# rs232_12V_step_Vadim.net
KiCad netlist of a schematic drawn in Altium Designer
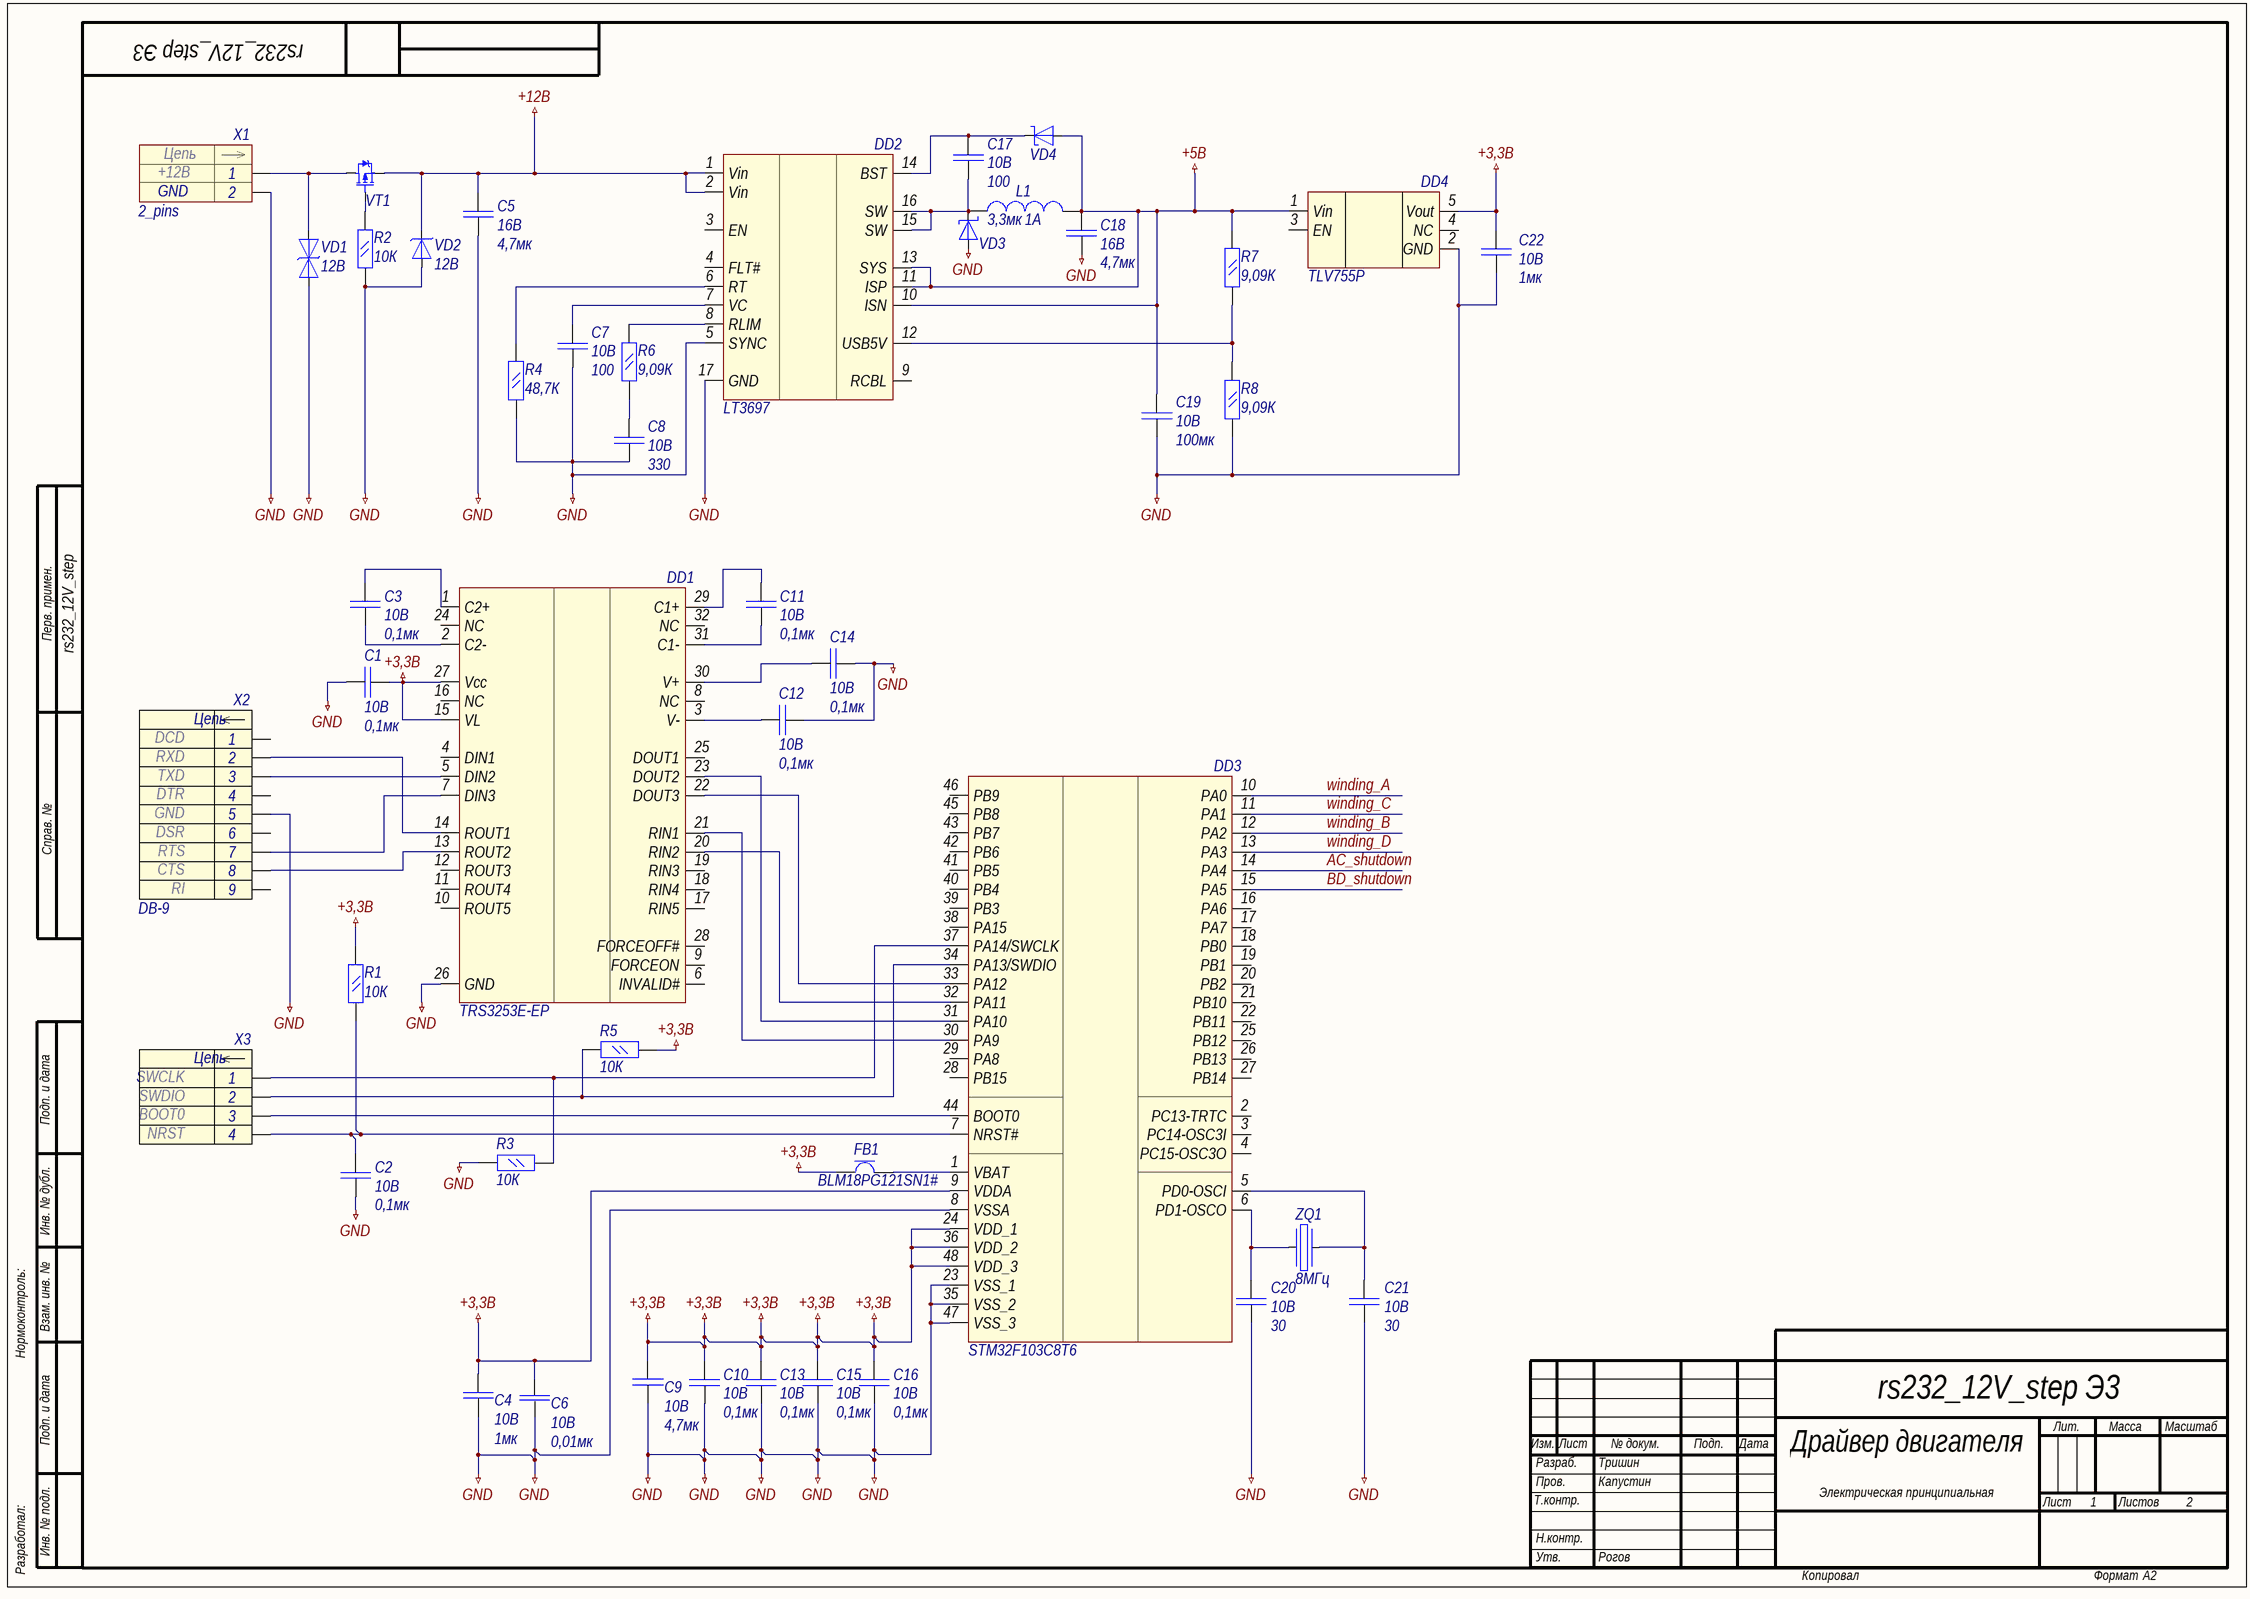
[diagram p0: rs232_12V_step_Vadim.SchDoc]

(export (version "E")
  (design (tool "Eeschema 10.0.6"))
  (components
    (comp (ref "C1")
      (value "Capacitor")
      (footprint "CH0402C")
      (fields (field (name "VOLTAGE") "10В") (field (name "CAPACITANCE") "0,1мк"))
      (libsource (lib "GOST_Capacitors") (part "Capacitor"))
    )
    (comp (ref "C2")
      (value "Capacitor")
      (footprint "CH0402C")
      (fields (field (name "VOLTAGE") "10В") (field (name "CAPACITANCE") "0,1мк"))
      (libsource (lib "GOST_Capacitors") (part "Capacitor"))
    )
    (comp (ref "C3")
      (value "Capacitor")
      (footprint "CH0402C")
      (fields (field (name "VOLTAGE") "10В") (field (name "CAPACITANCE") "0,1мк"))
      (libsource (lib "GOST_Capacitors") (part "Capacitor"))
    )
    (comp (ref "C4")
      (value "Capacitor")
      (footprint "CH0201C")
      (fields (field (name "VOLTAGE") "10В") (field (name "CAPACITANCE") "1мк"))
      (libsource (lib "GOST_Capacitors") (part "Capacitor"))
    )
    (comp (ref "C5")
      (value "Capacitor")
      (footprint "CH0603C")
      (fields (field (name "VOLTAGE") "16В") (field (name "CAPACITANCE") "4,7мк"))
      (libsource (lib "GOST_Capacitors") (part "Capacitor"))
    )
    (comp (ref "C6")
      (value "Capacitor")
      (footprint "CH0402C")
      (fields (field (name "VOLTAGE") "10В") (field (name "CAPACITANCE") "0,01мк"))
      (libsource (lib "") (part "Capacitor_1"))
    )
    (comp (ref "C7")
      (value "Capacitor")
      (footprint "CH0201C")
      (fields (field (name "VOLTAGE") "10В") (field (name "CAPACITANCE") "100"))
      (libsource (lib "GOST_Capacitors") (part "Capacitor"))
    )
    (comp (ref "C8")
      (value "Capacitor")
      (footprint "CH0402C")
      (fields (field (name "VOLTAGE") "10В") (field (name "CAPACITANCE") "330"))
      (libsource (lib "GOST_Capacitors") (part "Capacitor"))
    )
    (comp (ref "C9")
      (value "Capacitor")
      (footprint "CH0402C")
      (fields (field (name "VOLTAGE") "10В") (field (name "CAPACITANCE") "4,7мк"))
      (libsource (lib "GOST_Capacitors") (part "Capacitor"))
    )
    (comp (ref "C10")
      (value "Capacitor")
      (footprint "CH0402C")
      (fields (field (name "VOLTAGE") "10В") (field (name "CAPACITANCE") "0,1мк"))
      (libsource (lib "GOST_Capacitors") (part "Capacitor"))
    )
    (comp (ref "C11")
      (value "Capacitor")
      (footprint "CH0402C")
      (fields (field (name "VOLTAGE") "10В") (field (name "CAPACITANCE") "0,1мк"))
      (libsource (lib "GOST_Capacitors") (part "Capacitor"))
    )
    (comp (ref "C12")
      (value "Capacitor")
      (footprint "CH0402C")
      (fields (field (name "VOLTAGE") "10В") (field (name "CAPACITANCE") "0,1мк"))
      (libsource (lib "GOST_Capacitors") (part "Capacitor"))
    )
    (comp (ref "C13")
      (value "Capacitor")
      (footprint "CH0402C")
      (fields (field (name "VOLTAGE") "10В") (field (name "CAPACITANCE") "0,1мк"))
      (libsource (lib "GOST_Capacitors") (part "Capacitor"))
    )
    (comp (ref "C14")
      (value "Capacitor")
      (footprint "CH0402C")
      (fields (field (name "VOLTAGE") "10В") (field (name "CAPACITANCE") "0,1мк"))
      (libsource (lib "GOST_Capacitors") (part "Capacitor"))
    )
    (comp (ref "C15")
      (value "Capacitor")
      (footprint "CH0402C")
      (fields (field (name "VOLTAGE") "10В") (field (name "CAPACITANCE") "0,1мк"))
      (libsource (lib "GOST_Capacitors") (part "Capacitor"))
    )
    (comp (ref "C16")
      (value "Capacitor")
      (footprint "CH0402C")
      (fields (field (name "VOLTAGE") "10В") (field (name "CAPACITANCE") "0,1мк"))
      (libsource (lib "GOST_Capacitors") (part "Capacitor"))
    )
    (comp (ref "C17")
      (value "Capacitor")
      (footprint "CH0201C")
      (fields (field (name "VOLTAGE") "10В") (field (name "CAPACITANCE") "100"))
      (libsource (lib "GOST_Capacitors") (part "Capacitor"))
    )
    (comp (ref "C18")
      (value "Capacitor")
      (footprint "CH0603C")
      (fields (field (name "VOLTAGE") "16В") (field (name "CAPACITANCE") "4,7мк"))
      (libsource (lib "GOST_Capacitors") (part "Capacitor"))
    )
    (comp (ref "C19")
      (value "Capacitor")
      (footprint "CH1206C")
      (fields (field (name "VOLTAGE") "10В") (field (name "CAPACITANCE") "100мк"))
      (libsource (lib "GOST_Capacitors") (part "Capacitor"))
    )
    (comp (ref "C20")
      (value "Capacitor")
      (footprint "CH0201C")
      (fields (field (name "VOLTAGE") "10В") (field (name "CAPACITANCE") "30"))
      (libsource (lib "GOST_Capacitors") (part "Capacitor"))
    )
    (comp (ref "C21")
      (value "Capacitor")
      (footprint "CH0201C")
      (fields (field (name "VOLTAGE") "10В") (field (name "CAPACITANCE") "30"))
      (libsource (lib "GOST_Capacitors") (part "Capacitor"))
    )
    (comp (ref "C22")
      (value "Capacitor")
      (footprint "CH0201C")
      (fields (field (name "VOLTAGE") "10В") (field (name "CAPACITANCE") "1мк"))
      (libsource (lib "GOST_Capacitors") (part "Capacitor"))
    )
    (comp (ref "DD1")
      (value "TRS3253E-EP")
      (footprint "TRS3253E-EP")
      (description "UART - RS232")
      (libsource (lib "GOST_lib_devices") (part "TRS3253E-EP"))
    )
    (comp (ref "DD2")
      (value "LT3697")
      (footprint "LT3697")
      (description "6~18 to 5")
      (libsource (lib "GOST_lib_devices") (part "LT3697"))
    )
    (comp (ref "DD3")
      (value "STM32F103C8T6")
      (footprint "STM32F103 48pins")
      (libsource (lib "GOST_lib_devices") (part "STM32"))
    )
    (comp (ref "DD4")
      (value "TLV755P")
      (footprint "SOT23-5")
      (libsource (lib "GOST_lib_devices") (part "LDO +3.3V"))
    )
    (comp (ref "FB1")
      (value "Ferrite bead")
      (footprint "CH0603L")
      (fields (field (name "MODEL") "BLM18PG121SN1#"))
      (libsource (lib "GOST_Inductors") (part "Ferrite bead"))
    )
    (comp (ref "L1")
      (value "*")
      (footprint "CH0805L")
      (fields (field (name "MAX CURRENT") "1А") (field (name "INDUCTANCE") "3,3мк"))
      (libsource (lib "GOST_Inductors") (part "Inductor"))
    )
    (comp (ref "R1")
      (value "Res_0.125")
      (footprint "CH0805R")
      (fields (field (name "IMPEDANCE") "10К"))
      (libsource (lib "GOST_Resistors") (part "Res_0.125"))
    )
    (comp (ref "R2")
      (value "Res_0.125")
      (footprint "CH0402R")
      (fields (field (name "IMPEDANCE") "10К"))
      (libsource (lib "GOST_Resistors") (part "Res_0.125"))
    )
    (comp (ref "R3")
      (value "Res_0.125")
      (footprint "CH0805R")
      (fields (field (name "IMPEDANCE") "10К"))
      (libsource (lib "GOST_Resistors") (part "Res_0.125"))
    )
    (comp (ref "R4")
      (value "Res_0.125")
      (footprint "CH0805R")
      (fields (field (name "IMPEDANCE") "48,7К"))
      (libsource (lib "GOST_Resistors") (part "Res_0.125"))
    )
    (comp (ref "R5")
      (value "Res_0.125")
      (footprint "CH0805R")
      (fields (field (name "IMPEDANCE") "10К"))
      (libsource (lib "GOST_Resistors") (part "Res_0.125"))
    )
    (comp (ref "R6")
      (value "Res_0.125")
      (footprint "CH0805R")
      (fields (field (name "IMPEDANCE") "9,09К"))
      (libsource (lib "GOST_Resistors") (part "Res_0.125"))
    )
    (comp (ref "R7")
      (value "Res_0.125")
      (footprint "CH0805R")
      (fields (field (name "IMPEDANCE") "9,09К"))
      (libsource (lib "GOST_Resistors") (part "Res_0.125"))
    )
    (comp (ref "R8")
      (value "Res_0.125")
      (footprint "CH0805R")
      (fields (field (name "IMPEDANCE") "9,09К"))
      (libsource (lib "GOST_Resistors") (part "Res_0.125"))
    )
    (comp (ref "VD1")
      (value "TVS-diod_simmetrical")
      (footprint "CH0201L")
      (fields (field (name "MANUFACTURER") "Littelfuse") (field (name "CLAMPING VOLTAGE") "12В"))
      (libsource (lib "GOST_Diodes") (part "TVS-diod_simmetrical"))
    )
    (comp (ref "VD2")
      (value "TVS-diod_directed")
      (footprint "DO214AA")
      (fields (field (name "MANUFACTURER") "Bourns") (field (name "CLAMPING_VOLTAGE") "12В"))
      (libsource (lib "GOST_Diodes") (part "TVS-diod_directed"))
    )
    (comp (ref "VD3")
      (value "Diod Schottky")
      (footprint "DO214AA")
      (fields (field (name "MANUFACTURER") "Rectron"))
      (libsource (lib "GOST_Diodes") (part "Diod Schottky"))
    )
    (comp (ref "VD4")
      (value "Diod Schottky")
      (footprint "SOT23_132")
      (fields (field (name "MANUFACTURER") "Toshiba"))
      (libsource (lib "GOST_Diodes") (part "Diod Schottky"))
    )
    (comp (ref "VT1")
      (value "*")
      (footprint "SOT23_132")
      (libsource (lib "GOST_Transistors") (part "P-Channel"))
    )
    (comp (ref "X1")
      (value "2_pins")
      (footprint "CON: 163-179PH-EX")
      (fields (field (name "VCC") "+12В"))
      (libsource (lib "GOST_lib_connectors") (part "2_pins"))
    )
    (comp (ref "X2")
      (value "DB-9")
      (footprint "CON: DB-9F")
      (fields
        (field (name "1") "DCD")
        (field (name "2") "RXD")
        (field (name "3") "TXD")
        (field (name "4") "DTR")
        (field (name "5") "GND")
        (field (name "6") "DSR")
        (field (name "7") "RTS")
        (field (name "8") "CTS")
        (field (name "9") "RI")
      )
      (libsource (lib "GOST_lib_connectors") (part "9_pins"))
    )
    (comp (ref "X3")
      (value "4_pins")
      (footprint "CON: CWF-4R")
      (fields
        (field (name "2") "SWDIO")
        (field (name "3") "BOOT0")
        (field (name "1") "SWCLK")
        (field (name "4") "NRST")
      )
      (libsource (lib "GOST_lib_connectors") (part "4_pins"))
    )
    (comp (ref "ZQ1")
      (value "Oscillator")
      (footprint "OSC: 5032")
      (fields (field (name "FREQ") "8МГц"))
      (libsource (lib "GOST_Miscelanuious") (part "Oscillator"))
    )
  )
  (nets
    (net (code "1") (name "+3,3В") (class "Default")
      (node (ref "C1") (pin "2") (pinfunction "C1-_2") (pintype "power_in"))
      (node (ref "C10") (pin "1") (pinfunction "C1+_1") (pintype "power_in"))
      (node (ref "C13") (pin "1") (pinfunction "C1+_1") (pintype "power_in"))
      (node (ref "C15") (pin "1") (pinfunction "C1+_1") (pintype "power_in"))
      (node (ref "C16") (pin "1") (pinfunction "C1+_1") (pintype "power_in"))
      (node (ref "C22") (pin "1") (pinfunction "C1+_1") (pintype "power_in"))
      (node (ref "C4") (pin "2") (pinfunction "C1-_2") (pintype "power_in"))
      (node (ref "C6") (pin "1") (pinfunction "С+_1") (pintype "power_in"))
      (node (ref "C9") (pin "2") (pinfunction "C1-_2") (pintype "power_in"))
      (node (ref "DD1") (pin "15") (pinfunction "VL_15") (pintype "power_in"))
      (node (ref "DD1") (pin "27") (pinfunction "Vcc_27") (pintype "power_in"))
      (node (ref "DD3") (pin "24") (pinfunction "VDD_1_24") (pintype "passive"))
      (node (ref "DD3") (pin "36") (pinfunction "VDD_2_36") (pintype "passive"))
      (node (ref "DD3") (pin "48") (pinfunction "VDD_3_48") (pintype "passive"))
      (node (ref "DD3") (pin "9") (pinfunction "VDDA_9") (pintype "passive"))
      (node (ref "DD4") (pin "5") (pinfunction "Vout_5") (pintype "power_in"))
      (node (ref "FB1") (pin "1") (pintype "power_in"))
      (node (ref "R1") (pin "1") (pinfunction "C1-_1") (pintype "power_in"))
      (node (ref "R5") (pin "2") (pinfunction "C1-_2") (pintype "power_in"))
    )
    (net (code "2") (name "+5В") (class "Default")
      (node (ref "C18") (pin "1") (pinfunction "C1+_1") (pintype "power_in"))
      (node (ref "C19") (pin "1") (pinfunction "C1+_1") (pintype "power_in"))
      (node (ref "DD2") (pin "10") (pinfunction "ISN_10") (pintype "power_in"))
      (node (ref "DD2") (pin "11") (pinfunction "ISP_11") (pintype "power_in"))
      (node (ref "DD2") (pin "13") (pinfunction "SYS_13") (pintype "power_in"))
      (node (ref "DD4") (pin "1") (pinfunction "Vin_1") (pintype "power_in"))
      (node (ref "L1") (pin "2") (pinfunction "14_2") (pintype "power_in"))
      (node (ref "R7") (pin "1") (pinfunction "C1-_1") (pintype "power_in"))
      (node (ref "VD4") (pin "1") (pinfunction "1_1") (pintype "passive"))
    )
    (net (code "3") (name "+12В") (class "Default")
      (node (ref "C5") (pin "1") (pinfunction "C1+_1") (pintype "power_in"))
      (node (ref "DD2") (pin "1") (pinfunction "Vin_1") (pintype "power_in"))
      (node (ref "DD2") (pin "2") (pinfunction "Vin_2") (pintype "power_in"))
      (node (ref "VD2") (pin "2") (pinfunction "C_2") (pintype "passive"))
      (node (ref "VT1") (pin "3") (pinfunction "S_3") (pintype "passive"))
    )
    (net (code "4") (name "/AC_shutdown") (class "Default")
      (node (ref "DD3") (pin "14") (pinfunction "PA4_14") (pintype "passive"))
    )
    (net (code "5") (name "/BD_shutdown") (class "Default")
      (node (ref "DD3") (pin "15") (pinfunction "PA5_15") (pintype "passive"))
    )
    (net (code "6") (name "/winding_A") (class "Default")
      (node (ref "DD3") (pin "10") (pinfunction "PA0_10") (pintype "passive"))
    )
    (net (code "7") (name "/winding_B") (class "Default")
      (node (ref "DD3") (pin "12") (pinfunction "PA2_12") (pintype "passive"))
    )
    (net (code "8") (name "/winding_C") (class "Default")
      (node (ref "DD3") (pin "11") (pinfunction "PA1_11") (pintype "passive"))
    )
    (net (code "9") (name "/winding_D") (class "Default")
      (node (ref "DD3") (pin "13") (pinfunction "PA3_13") (pintype "passive"))
    )
    (net (code "10") (name "GND") (class "Default")
      (node (ref "C1") (pin "1") (pinfunction "C1+_1") (pintype "power_in"))
      (node (ref "C10") (pin "2") (pinfunction "C1-_2") (pintype "power_in"))
      (node (ref "C12") (pin "2") (pinfunction "C1-_2") (pintype "power_in"))
      (node (ref "C13") (pin "2") (pinfunction "C1-_2") (pintype "power_in"))
      (node (ref "C14") (pin "2") (pinfunction "C1-_2") (pintype "power_in"))
      (node (ref "C15") (pin "2") (pinfunction "C1-_2") (pintype "power_in"))
      (node (ref "C16") (pin "2") (pinfunction "C1-_2") (pintype "power_in"))
      (node (ref "C18") (pin "2") (pinfunction "C1-_2") (pintype "power_in"))
      (node (ref "C19") (pin "2") (pinfunction "C1-_2") (pintype "power_in"))
      (node (ref "C2") (pin "2") (pinfunction "C1-_2") (pintype "power_in"))
      (node (ref "C20") (pin "2") (pinfunction "C1-_2") (pintype "power_in"))
      (node (ref "C21") (pin "2") (pinfunction "C1-_2") (pintype "power_in"))
      (node (ref "C22") (pin "2") (pinfunction "C1-_2") (pintype "power_in"))
      (node (ref "C4") (pin "1") (pinfunction "C1+_1") (pintype "power_in"))
      (node (ref "C5") (pin "2") (pinfunction "C1-_2") (pintype "power_in"))
      (node (ref "C6") (pin "2") (pinfunction "С-_2") (pintype "power_in"))
      (node (ref "C7") (pin "2") (pinfunction "C1-_2") (pintype "power_in"))
      (node (ref "C8") (pin "2") (pinfunction "C1-_2") (pintype "power_in"))
      (node (ref "C9") (pin "1") (pinfunction "C1+_1") (pintype "power_in"))
      (node (ref "DD1") (pin "26") (pinfunction "GND_26") (pintype "power_in"))
      (node (ref "DD2") (pin "17") (pinfunction "GND_17") (pintype "power_in"))
      (node (ref "DD2") (pin "5") (pinfunction "SYNC_5") (pintype "power_in"))
      (node (ref "DD3") (pin "23") (pinfunction "VSS_1_23") (pintype "passive"))
      (node (ref "DD3") (pin "35") (pinfunction "VSS_2_35") (pintype "passive"))
      (node (ref "DD3") (pin "47") (pinfunction "VSS_3_47") (pintype "passive"))
      (node (ref "DD3") (pin "8") (pinfunction "VSSA_8") (pintype "passive"))
      (node (ref "DD4") (pin "2") (pinfunction "GND_2") (pintype "power_in"))
      (node (ref "R2") (pin "1") (pinfunction "C1-_1") (pintype "power_in"))
      (node (ref "R3") (pin "1") (pinfunction "C1-_1") (pintype "power_in"))
      (node (ref "R4") (pin "2") (pinfunction "C1-_2") (pintype "power_in"))
      (node (ref "R8") (pin "2") (pinfunction "C1-_2") (pintype "power_in"))
      (node (ref "VD1") (pin "1") (pinfunction "A_1") (pintype "passive"))
      (node (ref "VD2") (pin "1") (pinfunction "A_1") (pintype "passive"))
      (node (ref "VD3") (pin "1") (pinfunction "1_1") (pintype "passive"))
      (node (ref "X1") (pin "2") (pinfunction "2_2") (pintype "passive"))
      (node (ref "X2") (pin "5") (pinfunction "5_5") (pintype "passive"))
    )
    (net (code "11") (name "Net-(C2-C1+)") (class "Default")
      (node (ref "C2") (pin "1") (pinfunction "C1+_1") (pintype "power_in"))
      (node (ref "DD3") (pin "7") (pinfunction "NRST#_7") (pintype "passive"))
      (node (ref "R1") (pin "2") (pinfunction "C1-_2") (pintype "power_in"))
      (node (ref "X3") (pin "4") (pinfunction "4_4") (pintype "passive"))
    )
    (net (code "12") (name "Net-(C3-C1+)") (class "Default")
      (node (ref "C3") (pin "1") (pinfunction "C1+_1") (pintype "power_in"))
      (node (ref "DD1") (pin "1") (pinfunction "C2+_1") (pintype "power_in"))
    )
    (net (code "13") (name "Net-(C3-C1-)") (class "Default")
      (node (ref "C3") (pin "2") (pinfunction "C1-_2") (pintype "power_in"))
      (node (ref "DD1") (pin "2") (pinfunction "C2-_2") (pintype "power_in"))
    )
    (net (code "14") (name "Net-(C7-C1+)") (class "Default")
      (node (ref "C7") (pin "1") (pinfunction "C1+_1") (pintype "power_in"))
      (node (ref "DD2") (pin "7") (pinfunction "VC_7") (pintype "power_in"))
    )
    (net (code "15") (name "Net-(C8-C1+)") (class "Default")
      (node (ref "C8") (pin "1") (pinfunction "C1+_1") (pintype "power_in"))
      (node (ref "R6") (pin "2") (pinfunction "C1-_2") (pintype "power_in"))
    )
    (net (code "16") (name "Net-(C11-C1+)") (class "Default")
      (node (ref "C11") (pin "1") (pinfunction "C1+_1") (pintype "power_in"))
      (node (ref "DD1") (pin "29") (pinfunction "C1+_29") (pintype "power_in"))
    )
    (net (code "17") (name "Net-(C11-C1-)") (class "Default")
      (node (ref "C11") (pin "2") (pinfunction "C1-_2") (pintype "power_in"))
      (node (ref "DD1") (pin "31") (pinfunction "C1-_31") (pintype "power_in"))
    )
    (net (code "18") (name "Net-(C12-C1+)") (class "Default")
      (node (ref "C12") (pin "1") (pinfunction "C1+_1") (pintype "power_in"))
      (node (ref "DD1") (pin "3") (pinfunction "V-_3") (pintype "power_in"))
    )
    (net (code "19") (name "Net-(C14-C1+)") (class "Default")
      (node (ref "C14") (pin "1") (pinfunction "C1+_1") (pintype "power_in"))
      (node (ref "DD1") (pin "30") (pinfunction "V+_30") (pintype "power_in"))
    )
    (net (code "20") (name "Net-(C17-C1+)") (class "Default")
      (node (ref "C17") (pin "1") (pinfunction "C1+_1") (pintype "power_in"))
      (node (ref "DD2") (pin "14") (pinfunction "BST_14") (pintype "power_in"))
      (node (ref "VD4") (pin "2") (pinfunction "2_2") (pintype "passive"))
    )
    (net (code "21") (name "Net-(C17-C1-)") (class "Default")
      (node (ref "C17") (pin "2") (pinfunction "C1-_2") (pintype "power_in"))
      (node (ref "DD2") (pin "15") (pinfunction "SW_15") (pintype "power_in"))
      (node (ref "DD2") (pin "16") (pinfunction "SW_16") (pintype "power_in"))
      (node (ref "L1") (pin "1") (pinfunction "C1-_1") (pintype "power_in"))
      (node (ref "VD3") (pin "2") (pinfunction "2_2") (pintype "passive"))
    )
    (net (code "22") (name "Net-(C20-C1+)") (class "Default")
      (node (ref "C20") (pin "1") (pinfunction "C1+_1") (pintype "power_in"))
      (node (ref "DD3") (pin "6") (pinfunction "PD1-OSCO_6") (pintype "passive"))
      (node (ref "ZQ1") (pin "1") (pintype "passive"))
    )
    (net (code "23") (name "Net-(C21-C1+)") (class "Default")
      (node (ref "C21") (pin "1") (pinfunction "C1+_1") (pintype "power_in"))
      (node (ref "DD3") (pin "5") (pinfunction "PD0-OSCI_5") (pintype "passive"))
      (node (ref "ZQ1") (pin "3") (pintype "passive"))
    )
    (net (code "24") (name "Net-(DD1-DIN2)") (class "Default")
      (node (ref "DD1") (pin "5") (pinfunction "DIN2_5") (pintype "power_in"))
      (node (ref "X2") (pin "3") (pinfunction "3_3") (pintype "passive"))
    )
    (net (code "25") (name "Net-(DD1-DIN3)") (class "Default")
      (node (ref "DD1") (pin "7") (pinfunction "DIN3_7") (pintype "power_in"))
      (node (ref "X2") (pin "7") (pinfunction "7_7") (pintype "power_in"))
    )
    (net (code "26") (name "Net-(DD1-DOUT2)") (class "Default")
      (node (ref "DD1") (pin "23") (pinfunction "DOUT2_23") (pintype "power_in"))
      (node (ref "DD3") (pin "31") (pinfunction "PA10_31") (pintype "passive"))
    )
    (net (code "27") (name "Net-(DD1-DOUT3)") (class "Default")
      (node (ref "DD1") (pin "22") (pinfunction "DOUT3_22") (pintype "power_in"))
      (node (ref "DD3") (pin "33") (pinfunction "PA12_33") (pintype "passive"))
    )
    (net (code "28") (name "Net-(DD1-RIN1)") (class "Default")
      (node (ref "DD1") (pin "21") (pinfunction "RIN1_21") (pintype "power_in"))
      (node (ref "DD3") (pin "30") (pinfunction "PA9_30") (pintype "passive"))
    )
    (net (code "29") (name "Net-(DD1-RIN2)") (class "Default")
      (node (ref "DD1") (pin "20") (pinfunction "RIN2_20") (pintype "power_in"))
      (node (ref "DD3") (pin "32") (pinfunction "PA11_32") (pintype "passive"))
    )
    (net (code "30") (name "Net-(DD1-ROUT1)") (class "Default")
      (node (ref "DD1") (pin "14") (pinfunction "ROUT1_14") (pintype "power_in"))
      (node (ref "X2") (pin "2") (pinfunction "2_2") (pintype "passive"))
    )
    (net (code "31") (name "Net-(DD1-ROUT2)") (class "Default")
      (node (ref "DD1") (pin "13") (pinfunction "ROUT2_13") (pintype "power_in"))
      (node (ref "X2") (pin "8") (pinfunction "8_8") (pintype "power_in"))
    )
    (net (code "32") (name "Net-(DD2-RLIM)") (class "Default")
      (node (ref "DD2") (pin "8") (pinfunction "RLIM_8") (pintype "power_in"))
      (node (ref "R6") (pin "1") (pinfunction "C1-_1") (pintype "power_in"))
    )
    (net (code "33") (name "Net-(DD2-RT)") (class "Default")
      (node (ref "DD2") (pin "6") (pinfunction "RT_6") (pintype "power_in"))
      (node (ref "R4") (pin "1") (pinfunction "C1-_1") (pintype "power_in"))
    )
    (net (code "34") (name "Net-(DD2-USB5V)") (class "Default")
      (node (ref "DD2") (pin "12") (pinfunction "USB5V_12") (pintype "power_in"))
      (node (ref "R7") (pin "2") (pinfunction "C1-_2") (pintype "power_in"))
      (node (ref "R8") (pin "1") (pinfunction "C1-_1") (pintype "power_in"))
    )
    (net (code "35") (name "Net-(DD3-BOOT0)") (class "Default")
      (node (ref "DD3") (pin "44") (pinfunction "BOOT0_44") (pintype "passive"))
      (node (ref "X3") (pin "3") (pinfunction "3_3") (pintype "passive"))
    )
    (net (code "36") (name "Net-(DD3-PA13{slash}SWDIO)") (class "Default")
      (node (ref "DD3") (pin "34") (pinfunction "PA13/SWDIO_34") (pintype "passive"))
      (node (ref "R5") (pin "1") (pinfunction "C1-_1") (pintype "power_in"))
      (node (ref "X3") (pin "2") (pinfunction "2_2") (pintype "passive"))
    )
    (net (code "37") (name "Net-(DD3-PA14{slash}SWCLK)") (class "Default")
      (node (ref "DD3") (pin "37") (pinfunction "PA14/SWCLK_37") (pintype "passive"))
      (node (ref "R3") (pin "2") (pinfunction "C1-_2") (pintype "power_in"))
      (node (ref "X3") (pin "1") (pinfunction "1_1") (pintype "passive"))
    )
    (net (code "38") (name "Net-(DD3-VBAT)") (class "Default")
      (node (ref "DD3") (pin "1") (pinfunction "VBAT_1") (pintype "passive"))
      (node (ref "FB1") (pin "2") (pintype "power_in"))
    )
    (net (code "39") (name "Net-(VD1-C)") (class "Default")
      (node (ref "VD1") (pin "2") (pinfunction "C_2") (pintype "passive"))
      (node (ref "VT1") (pin "2") (pinfunction "D_2") (pintype "passive"))
      (node (ref "X1") (pin "1") (pinfunction "1_1") (pintype "passive"))
    )
    (net (code "40") (name "Net-(VT1-G)") (class "Default")
      (node (ref "R2") (pin "2") (pinfunction "C1-_2") (pintype "power_in"))
      (node (ref "VT1") (pin "1") (pinfunction "G_1") (pintype "passive"))
    )
    (net (code "41") (name "unconnected-(DD1-DIN1-Pad4)") (class "Default")
      (node (ref "DD1") (pin "4") (pinfunction "DIN1_4") (pintype "power_in"))
    )
    (net (code "42") (name "unconnected-(DD1-DOUT1-Pad25)") (class "Default")
      (node (ref "DD1") (pin "25") (pinfunction "DOUT1_25") (pintype "power_in"))
    )
    (net (code "43") (name "unconnected-(DD1-FORCEOFF#-Pad28)") (class "Default")
      (node (ref "DD1") (pin "28") (pinfunction "FORCEOFF#_28") (pintype "power_in"))
    )
    (net (code "44") (name "unconnected-(DD1-FORCEON-Pad9)") (class "Default")
      (node (ref "DD1") (pin "9") (pinfunction "FORCEON_9") (pintype "power_in"))
    )
    (net (code "45") (name "unconnected-(DD1-INVALID#-Pad6)") (class "Default")
      (node (ref "DD1") (pin "6") (pinfunction "INVALID#_6") (pintype "power_in"))
    )
    (net (code "46") (name "unconnected-(DD1-NC-Pad8)") (class "Default")
      (node (ref "DD1") (pin "8") (pinfunction "NC_8") (pintype "power_in"))
    )
    (net (code "47") (name "unconnected-(DD1-NC-Pad16)") (class "Default")
      (node (ref "DD1") (pin "16") (pinfunction "NC_16") (pintype "power_in"))
    )
    (net (code "48") (name "unconnected-(DD1-NC-Pad24)") (class "Default")
      (node (ref "DD1") (pin "24") (pinfunction "NC_24") (pintype "power_in"))
    )
    (net (code "49") (name "unconnected-(DD1-NC-Pad32)") (class "Default")
      (node (ref "DD1") (pin "32") (pinfunction "NC_32") (pintype "power_in"))
    )
    (net (code "50") (name "unconnected-(DD1-RIN3-Pad19)") (class "Default")
      (node (ref "DD1") (pin "19") (pinfunction "RIN3_19") (pintype "power_in"))
    )
    (net (code "51") (name "unconnected-(DD1-RIN4-Pad18)") (class "Default")
      (node (ref "DD1") (pin "18") (pinfunction "RIN4_18") (pintype "power_in"))
    )
    (net (code "52") (name "unconnected-(DD1-RIN5-Pad17)") (class "Default")
      (node (ref "DD1") (pin "17") (pinfunction "RIN5_17") (pintype "power_in"))
    )
    (net (code "53") (name "unconnected-(DD1-ROUT3-Pad12)") (class "Default")
      (node (ref "DD1") (pin "12") (pinfunction "ROUT3_12") (pintype "power_in"))
    )
    (net (code "54") (name "unconnected-(DD1-ROUT4-Pad11)") (class "Default")
      (node (ref "DD1") (pin "11") (pinfunction "ROUT4_11") (pintype "power_in"))
    )
    (net (code "55") (name "unconnected-(DD1-ROUT5-Pad10)") (class "Default")
      (node (ref "DD1") (pin "10") (pinfunction "ROUT5_10") (pintype "power_in"))
    )
    (net (code "56") (name "unconnected-(DD2-EN-Pad3)") (class "Default")
      (node (ref "DD2") (pin "3") (pinfunction "EN_3") (pintype "power_in"))
    )
    (net (code "57") (name "unconnected-(DD2-FLT#-Pad4)") (class "Default")
      (node (ref "DD2") (pin "4") (pinfunction "FLT#_4") (pintype "power_in"))
    )
    (net (code "58") (name "unconnected-(DD2-RCBL-Pad9)") (class "Default")
      (node (ref "DD2") (pin "9") (pinfunction "RCBL_9") (pintype "power_in"))
    )
    (net (code "59") (name "unconnected-(DD3-PA6-Pad16)") (class "Default")
      (node (ref "DD3") (pin "16") (pinfunction "PA6_16") (pintype "passive"))
    )
    (net (code "60") (name "unconnected-(DD3-PA7-Pad17)") (class "Default")
      (node (ref "DD3") (pin "17") (pinfunction "PA7_17") (pintype "passive"))
    )
    (net (code "61") (name "unconnected-(DD3-PA8-Pad29)") (class "Default")
      (node (ref "DD3") (pin "29") (pinfunction "PA8_29") (pintype "passive"))
    )
    (net (code "62") (name "unconnected-(DD3-PA15-Pad38)") (class "Default")
      (node (ref "DD3") (pin "38") (pinfunction "PA15_38") (pintype "passive"))
    )
    (net (code "63") (name "unconnected-(DD3-PB0-Pad18)") (class "Default")
      (node (ref "DD3") (pin "18") (pinfunction "PB0_18") (pintype "passive"))
    )
    (net (code "64") (name "unconnected-(DD3-PB1-Pad19)") (class "Default")
      (node (ref "DD3") (pin "19") (pinfunction "PB1_19") (pintype "passive"))
    )
    (net (code "65") (name "unconnected-(DD3-PB2-Pad20)") (class "Default")
      (node (ref "DD3") (pin "20") (pinfunction "PB2_20") (pintype "passive"))
    )
    (net (code "66") (name "unconnected-(DD3-PB3-Pad39)") (class "Default")
      (node (ref "DD3") (pin "39") (pinfunction "PB3_39") (pintype "passive"))
    )
    (net (code "67") (name "unconnected-(DD3-PB4-Pad40)") (class "Default")
      (node (ref "DD3") (pin "40") (pinfunction "PB4_40") (pintype "passive"))
    )
    (net (code "68") (name "unconnected-(DD3-PB5-Pad41)") (class "Default")
      (node (ref "DD3") (pin "41") (pinfunction "PB5_41") (pintype "passive"))
    )
    (net (code "69") (name "unconnected-(DD3-PB6-Pad42)") (class "Default")
      (node (ref "DD3") (pin "42") (pinfunction "PB6_42") (pintype "passive"))
    )
    (net (code "70") (name "unconnected-(DD3-PB7-Pad43)") (class "Default")
      (node (ref "DD3") (pin "43") (pinfunction "PB7_43") (pintype "passive"))
    )
    (net (code "71") (name "unconnected-(DD3-PB8-Pad45)") (class "Default")
      (node (ref "DD3") (pin "45") (pinfunction "PB8_45") (pintype "passive"))
    )
    (net (code "72") (name "unconnected-(DD3-PB9-Pad46)") (class "Default")
      (node (ref "DD3") (pin "46") (pinfunction "PB9_46") (pintype "passive"))
    )
    (net (code "73") (name "unconnected-(DD3-PB10-Pad21)") (class "Default")
      (node (ref "DD3") (pin "21") (pinfunction "PB10_21") (pintype "passive"))
    )
    (net (code "74") (name "unconnected-(DD3-PB11-Pad22)") (class "Default")
      (node (ref "DD3") (pin "22") (pinfunction "PB11_22") (pintype "passive"))
    )
    (net (code "75") (name "unconnected-(DD3-PB12-Pad25)") (class "Default")
      (node (ref "DD3") (pin "25") (pinfunction "PB12_25") (pintype "passive"))
    )
    (net (code "76") (name "unconnected-(DD3-PB13-Pad26)") (class "Default")
      (node (ref "DD3") (pin "26") (pinfunction "PB13_26") (pintype "passive"))
    )
    (net (code "77") (name "unconnected-(DD3-PB14-Pad27)") (class "Default")
      (node (ref "DD3") (pin "27") (pinfunction "PB14_27") (pintype "passive"))
    )
    (net (code "78") (name "unconnected-(DD3-PB15-Pad28)") (class "Default")
      (node (ref "DD3") (pin "28") (pinfunction "PB15_28") (pintype "passive"))
    )
    (net (code "79") (name "unconnected-(DD3-PC13-TRTC-Pad2)") (class "Default")
      (node (ref "DD3") (pin "2") (pinfunction "PC13-TRTC_2") (pintype "passive"))
    )
    (net (code "80") (name "unconnected-(DD3-PC14-OSC3I-Pad3)") (class "Default")
      (node (ref "DD3") (pin "3") (pinfunction "PC14-OSC3I_3") (pintype "passive"))
    )
    (net (code "81") (name "unconnected-(DD3-PC15-OSC3O-Pad4)") (class "Default")
      (node (ref "DD3") (pin "4") (pinfunction "PC15-OSC3O_4") (pintype "passive"))
    )
    (net (code "82") (name "unconnected-(DD4-EN-Pad3)") (class "Default")
      (node (ref "DD4") (pin "3") (pinfunction "EN_3") (pintype "power_in"))
    )
    (net (code "83") (name "unconnected-(DD4-NC-Pad4)") (class "Default")
      (node (ref "DD4") (pin "4") (pinfunction "NC_4") (pintype "power_in"))
    )
    (net (code "84") (name "unconnected-(X2-Pad1)") (class "Default")
      (node (ref "X2") (pin "1") (pinfunction "1_1") (pintype "passive"))
    )
    (net (code "85") (name "unconnected-(X2-Pad4)") (class "Default")
      (node (ref "X2") (pin "4") (pinfunction "4_4") (pintype "passive"))
    )
    (net (code "86") (name "unconnected-(X2-Pad6)") (class "Default")
      (node (ref "X2") (pin "6") (pinfunction "6_6") (pintype "passive"))
    )
    (net (code "87") (name "unconnected-(X2-Pad9)") (class "Default")
      (node (ref "X2") (pin "9") (pinfunction "9_9") (pintype "power_in"))
    )
  )
)
